# PowerSupply.net
KiCad netlist of a schematic drawn in Altium Designer
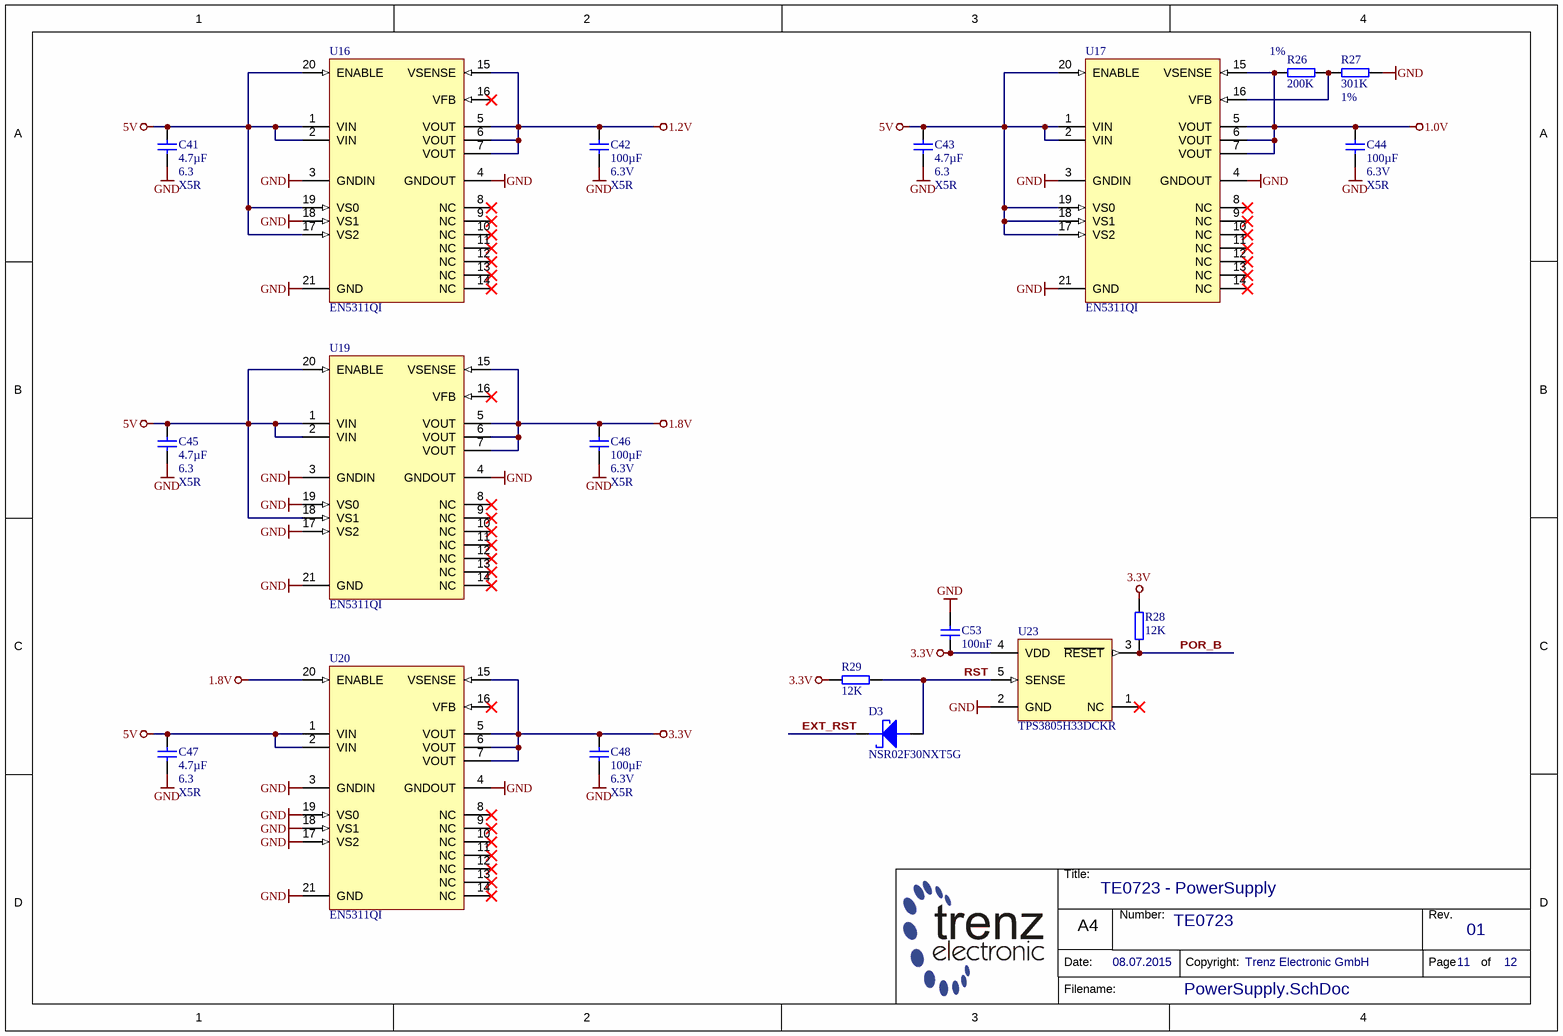
[diagram p0: PowerSupply.SchDoc]

(export (version "E")
  (design (tool "Eeschema 10.0.6"))
  (components
    (comp (ref "C41")
      (value "4.7µF")
      (footprint "CAPC1005X60N")
      (description "KON 4.7µF 6.3V X5R SMD 20%")
      (fields
        (field (name "VOLTAGE") "6.3")
        (field (name "TECHNOLOGY") "X5R")
        (field (name "TOLERANCE") "20%")
      )
      (libsource (lib "TE") (part "CAP-NP"))
    )
    (comp (ref "C42")
      (value "100µF")
      (footprint "CAPC3216X180N")
      (description "KON 100µF 6,3V X5R SMD 20%")
      (fields
        (field (name "VOLTAGE") "6.3V")
        (field (name "TECHNOLOGY") "X5R")
        (field (name "TOLERANCE") "20%")
      )
      (libsource (lib "TE") (part "CAP-NP"))
    )
    (comp (ref "C43")
      (value "4.7µF")
      (footprint "CAPC1005X60N")
      (description "KON 4.7µF 6.3V X5R SMD 20%")
      (fields
        (field (name "VOLTAGE") "6.3")
        (field (name "TECHNOLOGY") "X5R")
        (field (name "TOLERANCE") "20%")
      )
      (libsource (lib "TE") (part "CAP-NP"))
    )
    (comp (ref "C44")
      (value "100µF")
      (footprint "CAPC3216X180N")
      (description "KON 100µF 6,3V X5R SMD 20%")
      (fields
        (field (name "VOLTAGE") "6.3V")
        (field (name "TECHNOLOGY") "X5R")
        (field (name "TOLERANCE") "20%")
      )
      (libsource (lib "TE") (part "CAP-NP"))
    )
    (comp (ref "C45")
      (value "4.7µF")
      (footprint "CAPC1005X60N")
      (description "KON 4.7µF 6.3V X5R SMD 20%")
      (fields
        (field (name "VOLTAGE") "6.3")
        (field (name "TECHNOLOGY") "X5R")
        (field (name "TOLERANCE") "20%")
      )
      (libsource (lib "TE") (part "CAP-NP"))
    )
    (comp (ref "C46")
      (value "100µF")
      (footprint "CAPC3216X180N")
      (description "KON 100µF 6,3V X5R SMD 20%")
      (fields
        (field (name "VOLTAGE") "6.3V")
        (field (name "TECHNOLOGY") "X5R")
        (field (name "TOLERANCE") "20%")
      )
      (libsource (lib "TE") (part "CAP-NP"))
    )
    (comp (ref "C47")
      (value "4.7µF")
      (footprint "CAPC1005X60N")
      (description "KON 4.7µF 6.3V X5R SMD 20%")
      (fields
        (field (name "VOLTAGE") "6.3")
        (field (name "TECHNOLOGY") "X5R")
        (field (name "TOLERANCE") "20%")
      )
      (libsource (lib "TE") (part "CAP-NP"))
    )
    (comp (ref "C48")
      (value "100µF")
      (footprint "CAPC3216X180N")
      (description "KON 100µF 6,3V X5R SMD 20%")
      (fields
        (field (name "VOLTAGE") "6.3V")
        (field (name "TECHNOLOGY") "X5R")
        (field (name "TOLERANCE") "20%")
      )
      (libsource (lib "TE") (part "CAP-NP"))
    )
    (comp (ref "C53")
      (value "100nF")
      (footprint "CAPC1005X55N")
      (description "KON 100nF 50V SMD AEC-Q200")
      (fields (field (name "VOLTAGE") "50V") (field (name "TOLERANCE") "10%"))
      (libsource (lib "TE") (part "CAP-NP"))
    )
    (comp (ref "D3")
      (value "NSR02F30NXT5G")
      (footprint "DIOC0603X30N")
      (libsource (lib "TE") (part "SCHOTTKY"))
    )
    (comp (ref "R26")
      (value "200K")
      (footprint "RESC1005X40N")
      (description "WID SMD 200K 1% 0,063W")
      (fields (field (name "TOLERANCE") "1%"))
      (libsource (lib "TE") (part "RES"))
    )
    (comp (ref "R27")
      (value "301K")
      (footprint "RESC1005X40N")
      (description "WID SMD 301K 1% 0,063W")
      (fields (field (name "TOLERANCE") "1%"))
      (libsource (lib "TE") (part "RES"))
    )
    (comp (ref "R28")
      (value "12K")
      (footprint "RESC1005X40N")
      (description "WID SMD 12K 1% 0,063W")
      (libsource (lib "TE") (part "RES"))
    )
    (comp (ref "R29")
      (value "12K")
      (footprint "RESC1005X40N")
      (description "WID SMD 12K 1% 0,063W")
      (libsource (lib "TE") (part "RES"))
    )
    (comp (ref "U16") (value "EN5311QI") (footprint "EN5311QI") (libsource (lib "TE") (part "EN5311QI")))
    (comp (ref "U17") (value "EN5311QI") (footprint "EN5311QI") (libsource (lib "TE") (part "EN5311QI")))
    (comp (ref "U19") (value "EN5311QI") (footprint "EN5311QI") (libsource (lib "TE") (part "EN5311QI")))
    (comp (ref "U20") (value "EN5311QI") (footprint "EN5311QI") (libsource (lib "TE") (part "EN5311QI")))
    (comp (ref "U23")
      (value "TPS3805H33DCKR")
      (footprint "SOT65P210X110-5N")
      (libsource (lib "TE") (part "TPS3805H33DCK"))
    )
  )
  (nets
    (net (code "1") (name "/EXT_RST") (class "Default")
      (node (ref "D3") (pin "1") (pinfunction "KATHODE_1") (pintype "passive"))
    )
    (net (code "2") (name "/POR_B") (class "Default")
      (node (ref "R28") (pin "1") (pinfunction "1_1") (pintype "passive"))
      (node (ref "U23") (pin "3") (pinfunction "~{RESET}_3") (pintype "output"))
    )
    (net (code "3") (name "/RST") (class "Default")
      (node (ref "D3") (pin "2") (pinfunction "ANODE_2") (pintype "passive"))
      (node (ref "R29") (pin "1") (pinfunction "1_1") (pintype "passive"))
      (node (ref "U23") (pin "5") (pinfunction "SENSE_5") (pintype "input"))
    )
    (net (code "4") (name "1.0V") (class "Default")
      (node (ref "C44") (pin "1") (pinfunction "1_1") (pintype "passive"))
      (node (ref "R26") (pin "1") (pinfunction "1_1") (pintype "passive"))
      (node (ref "U17") (pin "15") (pinfunction "VSENSE_15") (pintype "input"))
      (node (ref "U17") (pin "5") (pinfunction "VOUT_5") (pintype "power_in"))
      (node (ref "U17") (pin "6") (pinfunction "VOUT_6") (pintype "power_in"))
      (node (ref "U17") (pin "7") (pinfunction "VOUT_7") (pintype "power_in"))
    )
    (net (code "5") (name "1.2V") (class "Default")
      (node (ref "C42") (pin "1") (pinfunction "1_1") (pintype "passive"))
      (node (ref "U16") (pin "15") (pinfunction "VSENSE_15") (pintype "input"))
      (node (ref "U16") (pin "5") (pinfunction "VOUT_5") (pintype "power_in"))
      (node (ref "U16") (pin "6") (pinfunction "VOUT_6") (pintype "power_in"))
      (node (ref "U16") (pin "7") (pinfunction "VOUT_7") (pintype "power_in"))
    )
    (net (code "6") (name "1.8V") (class "Default")
      (node (ref "C46") (pin "1") (pinfunction "1_1") (pintype "passive"))
      (node (ref "U19") (pin "15") (pinfunction "VSENSE_15") (pintype "input"))
      (node (ref "U19") (pin "5") (pinfunction "VOUT_5") (pintype "power_in"))
      (node (ref "U19") (pin "6") (pinfunction "VOUT_6") (pintype "power_in"))
      (node (ref "U19") (pin "7") (pinfunction "VOUT_7") (pintype "power_in"))
      (node (ref "U20") (pin "20") (pinfunction "ENABLE_20") (pintype "input"))
    )
    (net (code "7") (name "3.3V") (class "Default")
      (node (ref "C48") (pin "1") (pinfunction "1_1") (pintype "passive"))
      (node (ref "C53") (pin "2") (pinfunction "2_2") (pintype "passive"))
      (node (ref "R28") (pin "2") (pinfunction "2_2") (pintype "passive"))
      (node (ref "R29") (pin "2") (pinfunction "2_2") (pintype "passive"))
      (node (ref "U20") (pin "15") (pinfunction "VSENSE_15") (pintype "input"))
      (node (ref "U20") (pin "5") (pinfunction "VOUT_5") (pintype "power_in"))
      (node (ref "U20") (pin "6") (pinfunction "VOUT_6") (pintype "power_in"))
      (node (ref "U20") (pin "7") (pinfunction "VOUT_7") (pintype "power_in"))
      (node (ref "U23") (pin "4") (pinfunction "VDD_4") (pintype "power_in"))
    )
    (net (code "8") (name "5V") (class "Default")
      (node (ref "C41") (pin "1") (pinfunction "1_1") (pintype "passive"))
      (node (ref "C43") (pin "1") (pinfunction "1_1") (pintype "passive"))
      (node (ref "C45") (pin "1") (pinfunction "1_1") (pintype "passive"))
      (node (ref "C47") (pin "1") (pinfunction "1_1") (pintype "passive"))
      (node (ref "U16") (pin "1") (pinfunction "VIN_1") (pintype "power_in"))
      (node (ref "U16") (pin "17") (pinfunction "VS2_17") (pintype "input"))
      (node (ref "U16") (pin "19") (pinfunction "VS0_19") (pintype "input"))
      (node (ref "U16") (pin "2") (pinfunction "VIN_2") (pintype "power_in"))
      (node (ref "U16") (pin "20") (pinfunction "ENABLE_20") (pintype "input"))
      (node (ref "U17") (pin "1") (pinfunction "VIN_1") (pintype "power_in"))
      (node (ref "U17") (pin "17") (pinfunction "VS2_17") (pintype "input"))
      (node (ref "U17") (pin "18") (pinfunction "VS1_18") (pintype "input"))
      (node (ref "U17") (pin "19") (pinfunction "VS0_19") (pintype "input"))
      (node (ref "U17") (pin "2") (pinfunction "VIN_2") (pintype "power_in"))
      (node (ref "U17") (pin "20") (pinfunction "ENABLE_20") (pintype "input"))
      (node (ref "U19") (pin "1") (pinfunction "VIN_1") (pintype "power_in"))
      (node (ref "U19") (pin "18") (pinfunction "VS1_18") (pintype "input"))
      (node (ref "U19") (pin "2") (pinfunction "VIN_2") (pintype "power_in"))
      (node (ref "U19") (pin "20") (pinfunction "ENABLE_20") (pintype "input"))
      (node (ref "U20") (pin "1") (pinfunction "VIN_1") (pintype "power_in"))
      (node (ref "U20") (pin "2") (pinfunction "VIN_2") (pintype "power_in"))
    )
    (net (code "9") (name "GND") (class "Default")
      (node (ref "C41") (pin "2") (pinfunction "2_2") (pintype "passive"))
      (node (ref "C42") (pin "2") (pinfunction "2_2") (pintype "passive"))
      (node (ref "C43") (pin "2") (pinfunction "2_2") (pintype "passive"))
      (node (ref "C44") (pin "2") (pinfunction "2_2") (pintype "passive"))
      (node (ref "C45") (pin "2") (pinfunction "2_2") (pintype "passive"))
      (node (ref "C46") (pin "2") (pinfunction "2_2") (pintype "passive"))
      (node (ref "C47") (pin "2") (pinfunction "2_2") (pintype "passive"))
      (node (ref "C48") (pin "2") (pinfunction "2_2") (pintype "passive"))
      (node (ref "C53") (pin "1") (pinfunction "1_1") (pintype "passive"))
      (node (ref "R27") (pin "2") (pinfunction "2_2") (pintype "passive"))
      (node (ref "U16") (pin "18") (pinfunction "VS1_18") (pintype "input"))
      (node (ref "U16") (pin "21") (pinfunction "GND_21") (pintype "power_in"))
      (node (ref "U16") (pin "3") (pinfunction "GNDIN_3") (pintype "power_in"))
      (node (ref "U16") (pin "4") (pinfunction "GNDOUT_4") (pintype "power_in"))
      (node (ref "U17") (pin "21") (pinfunction "GND_21") (pintype "power_in"))
      (node (ref "U17") (pin "3") (pinfunction "GNDIN_3") (pintype "power_in"))
      (node (ref "U17") (pin "4") (pinfunction "GNDOUT_4") (pintype "power_in"))
      (node (ref "U19") (pin "17") (pinfunction "VS2_17") (pintype "input"))
      (node (ref "U19") (pin "19") (pinfunction "VS0_19") (pintype "input"))
      (node (ref "U19") (pin "21") (pinfunction "GND_21") (pintype "power_in"))
      (node (ref "U19") (pin "3") (pinfunction "GNDIN_3") (pintype "power_in"))
      (node (ref "U19") (pin "4") (pinfunction "GNDOUT_4") (pintype "power_in"))
      (node (ref "U20") (pin "17") (pinfunction "VS2_17") (pintype "input"))
      (node (ref "U20") (pin "18") (pinfunction "VS1_18") (pintype "input"))
      (node (ref "U20") (pin "19") (pinfunction "VS0_19") (pintype "input"))
      (node (ref "U20") (pin "21") (pinfunction "GND_21") (pintype "power_in"))
      (node (ref "U20") (pin "3") (pinfunction "GNDIN_3") (pintype "power_in"))
      (node (ref "U20") (pin "4") (pinfunction "GNDOUT_4") (pintype "power_in"))
      (node (ref "U23") (pin "2") (pinfunction "GND_2") (pintype "power_in"))
    )
    (net (code "10") (name "Net-(U17-VFB)") (class "Default")
      (node (ref "R26") (pin "2") (pinfunction "2_2") (pintype "passive"))
      (node (ref "R27") (pin "1") (pinfunction "1_1") (pintype "passive"))
      (node (ref "U17") (pin "16") (pinfunction "VFB_16") (pintype "input"))
    )
    (net (code "11") (name "unconnected-(U16-NC-Pad8)") (class "Default")
      (node (ref "U16") (pin "8") (pinfunction "NC_8") (pintype "passive+no_connect"))
    )
    (net (code "12") (name "unconnected-(U16-NC-Pad9)") (class "Default")
      (node (ref "U16") (pin "9") (pinfunction "NC_9") (pintype "passive+no_connect"))
    )
    (net (code "13") (name "unconnected-(U16-NC-Pad10)") (class "Default")
      (node (ref "U16") (pin "10") (pinfunction "NC_10") (pintype "passive+no_connect"))
    )
    (net (code "14") (name "unconnected-(U16-NC-Pad11)") (class "Default")
      (node (ref "U16") (pin "11") (pinfunction "NC_11") (pintype "passive+no_connect"))
    )
    (net (code "15") (name "unconnected-(U16-NC-Pad12)") (class "Default")
      (node (ref "U16") (pin "12") (pinfunction "NC_12") (pintype "passive+no_connect"))
    )
    (net (code "16") (name "unconnected-(U16-NC-Pad13)") (class "Default")
      (node (ref "U16") (pin "13") (pinfunction "NC_13") (pintype "passive+no_connect"))
    )
    (net (code "17") (name "unconnected-(U16-NC-Pad14)") (class "Default")
      (node (ref "U16") (pin "14") (pinfunction "NC_14") (pintype "passive+no_connect"))
    )
    (net (code "18") (name "unconnected-(U16-VFB-Pad16)") (class "Default")
      (node (ref "U16") (pin "16") (pinfunction "VFB_16") (pintype "input+no_connect"))
    )
    (net (code "19") (name "unconnected-(U17-NC-Pad8)") (class "Default")
      (node (ref "U17") (pin "8") (pinfunction "NC_8") (pintype "passive+no_connect"))
    )
    (net (code "20") (name "unconnected-(U17-NC-Pad9)") (class "Default")
      (node (ref "U17") (pin "9") (pinfunction "NC_9") (pintype "passive+no_connect"))
    )
    (net (code "21") (name "unconnected-(U17-NC-Pad10)") (class "Default")
      (node (ref "U17") (pin "10") (pinfunction "NC_10") (pintype "passive+no_connect"))
    )
    (net (code "22") (name "unconnected-(U17-NC-Pad11)") (class "Default")
      (node (ref "U17") (pin "11") (pinfunction "NC_11") (pintype "passive+no_connect"))
    )
    (net (code "23") (name "unconnected-(U17-NC-Pad12)") (class "Default")
      (node (ref "U17") (pin "12") (pinfunction "NC_12") (pintype "passive+no_connect"))
    )
    (net (code "24") (name "unconnected-(U17-NC-Pad13)") (class "Default")
      (node (ref "U17") (pin "13") (pinfunction "NC_13") (pintype "passive+no_connect"))
    )
    (net (code "25") (name "unconnected-(U17-NC-Pad14)") (class "Default")
      (node (ref "U17") (pin "14") (pinfunction "NC_14") (pintype "passive+no_connect"))
    )
    (net (code "26") (name "unconnected-(U19-NC-Pad8)") (class "Default")
      (node (ref "U19") (pin "8") (pinfunction "NC_8") (pintype "passive+no_connect"))
    )
    (net (code "27") (name "unconnected-(U19-NC-Pad9)") (class "Default")
      (node (ref "U19") (pin "9") (pinfunction "NC_9") (pintype "passive+no_connect"))
    )
    (net (code "28") (name "unconnected-(U19-NC-Pad10)") (class "Default")
      (node (ref "U19") (pin "10") (pinfunction "NC_10") (pintype "passive+no_connect"))
    )
    (net (code "29") (name "unconnected-(U19-NC-Pad11)") (class "Default")
      (node (ref "U19") (pin "11") (pinfunction "NC_11") (pintype "passive+no_connect"))
    )
    (net (code "30") (name "unconnected-(U19-NC-Pad12)") (class "Default")
      (node (ref "U19") (pin "12") (pinfunction "NC_12") (pintype "passive+no_connect"))
    )
    (net (code "31") (name "unconnected-(U19-NC-Pad13)") (class "Default")
      (node (ref "U19") (pin "13") (pinfunction "NC_13") (pintype "passive+no_connect"))
    )
    (net (code "32") (name "unconnected-(U19-NC-Pad14)") (class "Default")
      (node (ref "U19") (pin "14") (pinfunction "NC_14") (pintype "passive+no_connect"))
    )
    (net (code "33") (name "unconnected-(U19-VFB-Pad16)") (class "Default")
      (node (ref "U19") (pin "16") (pinfunction "VFB_16") (pintype "input+no_connect"))
    )
    (net (code "34") (name "unconnected-(U20-NC-Pad8)") (class "Default")
      (node (ref "U20") (pin "8") (pinfunction "NC_8") (pintype "passive+no_connect"))
    )
    (net (code "35") (name "unconnected-(U20-NC-Pad9)") (class "Default")
      (node (ref "U20") (pin "9") (pinfunction "NC_9") (pintype "passive+no_connect"))
    )
    (net (code "36") (name "unconnected-(U20-NC-Pad10)") (class "Default")
      (node (ref "U20") (pin "10") (pinfunction "NC_10") (pintype "passive+no_connect"))
    )
    (net (code "37") (name "unconnected-(U20-NC-Pad11)") (class "Default")
      (node (ref "U20") (pin "11") (pinfunction "NC_11") (pintype "passive+no_connect"))
    )
    (net (code "38") (name "unconnected-(U20-NC-Pad12)") (class "Default")
      (node (ref "U20") (pin "12") (pinfunction "NC_12") (pintype "passive+no_connect"))
    )
    (net (code "39") (name "unconnected-(U20-NC-Pad13)") (class "Default")
      (node (ref "U20") (pin "13") (pinfunction "NC_13") (pintype "passive+no_connect"))
    )
    (net (code "40") (name "unconnected-(U20-NC-Pad14)") (class "Default")
      (node (ref "U20") (pin "14") (pinfunction "NC_14") (pintype "passive+no_connect"))
    )
    (net (code "41") (name "unconnected-(U20-VFB-Pad16)") (class "Default")
      (node (ref "U20") (pin "16") (pinfunction "VFB_16") (pintype "input+no_connect"))
    )
    (net (code "42") (name "unconnected-(U23-NC-Pad1)") (class "Default")
      (node (ref "U23") (pin "1") (pinfunction "NC_1") (pintype "passive+no_connect"))
    )
  )
)
